# DB10012_ControlIOConnector.net
KiCad netlist of a schematic drawn in Altium Designer
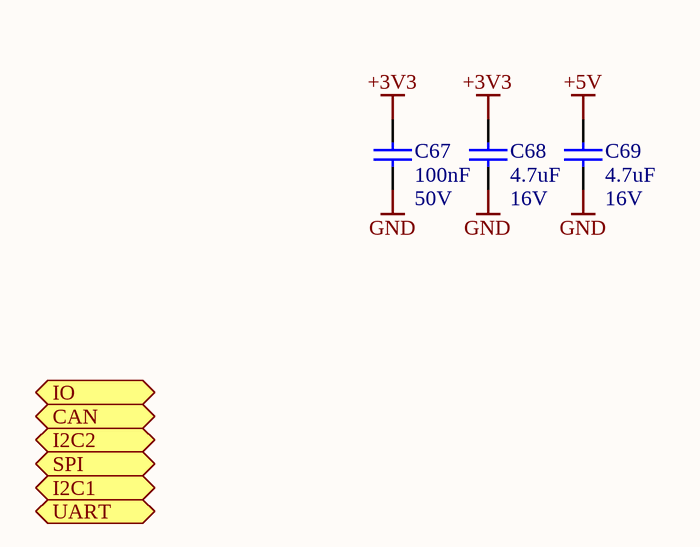
[diagram p0: DB10012_ControlIOConnector.SchDoc]

(export (version "E")
  (design (tool "Eeschema 10.0.6"))
  (components
    (comp (ref "C67")
      (value "100nF")
      (footprint "C-0805")
      (description "Capacitor, 100nF, 50V,  X7R")
      (fields (field (name "VOLTAGE RATING") "50V"))
      (libsource (lib "AR_Capacitors_Ceramic") (part "100nF/0805/CER/50V"))
    )
    (comp (ref "C68")
      (value "4.7uF")
      (footprint "C-0805")
      (description "Capacitor, 4.7uF, 16V, X7R")
      (fields (field (name "VOLTAGE RATING") "16V"))
      (libsource (lib "AR_Capacitors_Ceramic") (part "4.7uF/0805/CER/16V"))
    )
    (comp (ref "C69")
      (value "4.7uF")
      (footprint "C-0805")
      (description "Capacitor, 4.7uF, 16V, X7R")
      (fields (field (name "VOLTAGE RATING") "16V"))
      (libsource (lib "AR_Capacitors_Ceramic") (part "4.7uF/0805/CER/16V"))
    )
  )
  (nets
    (net (code "7") (name "+3V3") (class "Default")
      (node (ref "C67") (pin "2") (pinfunction "2_2") (pintype "passive"))
      (node (ref "C68") (pin "2") (pinfunction "2_2") (pintype "passive"))
    )
    (net (code "8") (name "+5V") (class "Default")
      (node (ref "C69") (pin "2") (pinfunction "2_2") (pintype "passive"))
    )
    (net (code "15") (name "GND") (class "Default")
      (node (ref "C67") (pin "1") (pinfunction "1_1") (pintype "passive"))
      (node (ref "C68") (pin "1") (pinfunction "1_1") (pintype "passive"))
      (node (ref "C69") (pin "1") (pinfunction "1_1") (pintype "passive"))
    )
  )
)
